# design.net
KiCad netlist of a schematic drawn in Altium Designer
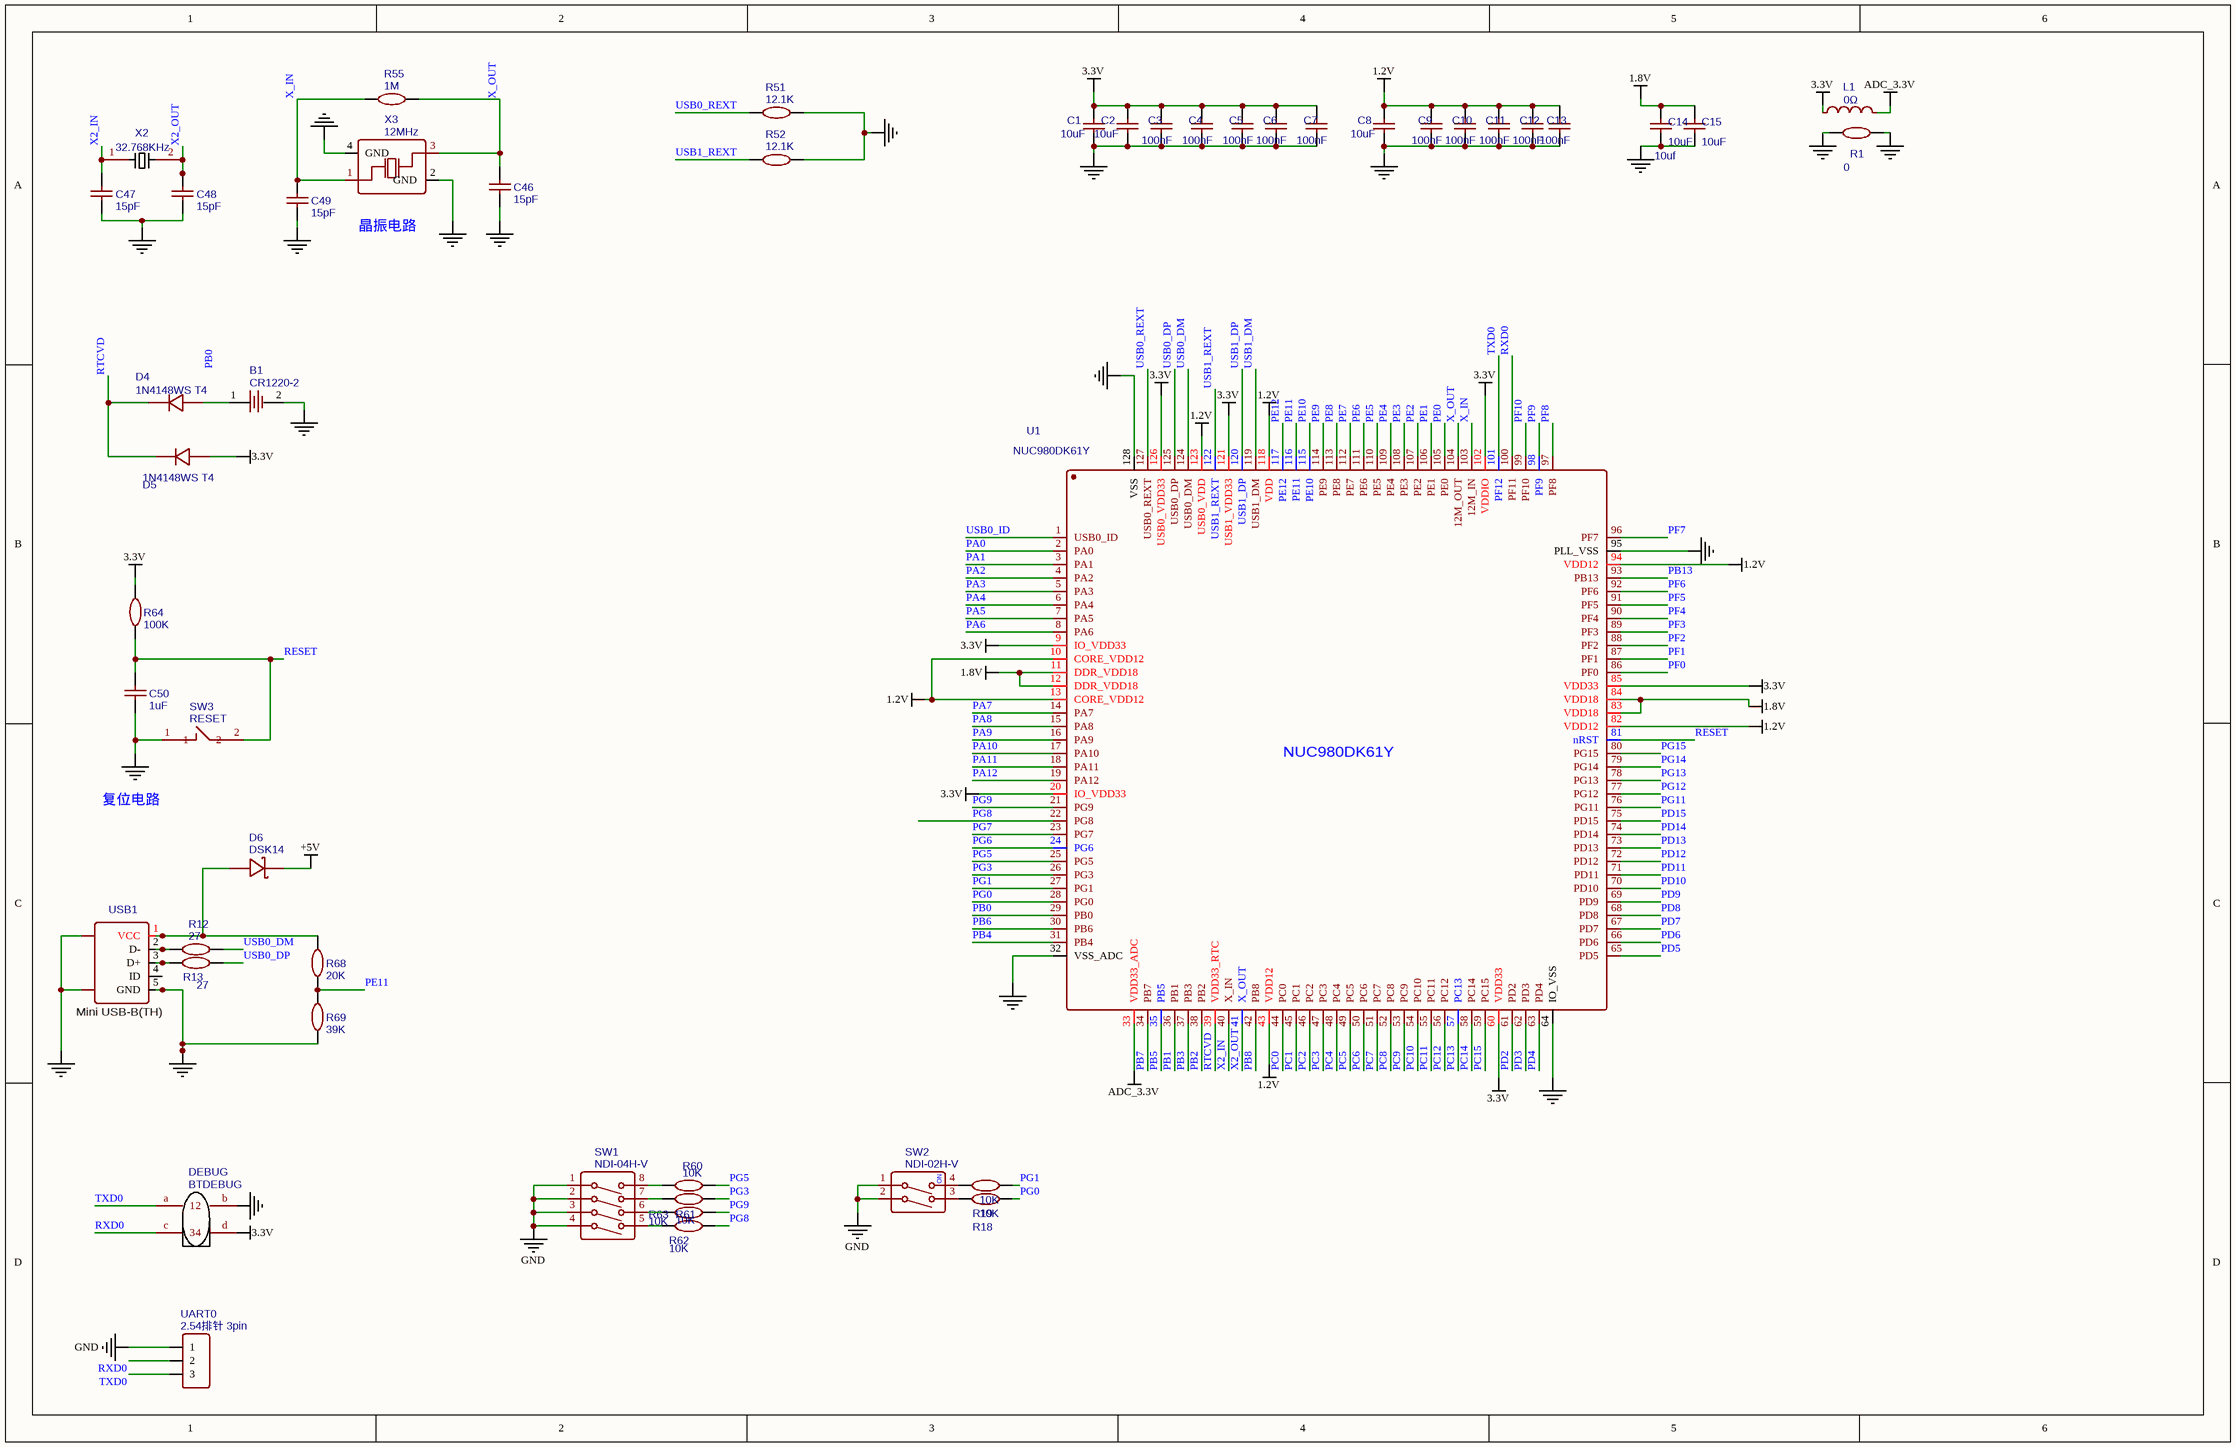
[diagram p0: 主控单元.schdoc]

(export (version "E")
  (design (tool "Eeschema 10.0.6"))
  (components
    (comp (ref "B1")
      (value "CR1220-2")
      (footprint "BATTERY-2")
      (fields (field (name "BOM_SUPPLIER PART") "C70381"))
      (libsource (lib "altium-import") (part "root_0_CR1220-2_"))
    )
    (comp (ref "C1")
      (value "10uF")
      (footprint "0805")
      (fields
        (field (name "BOM_MANUFACTURER PART") "CL21A106KAYNNNE")
        (field (name "BOM_SUPPLIER PART") "C15850")
      )
      (libsource (lib "altium-import") (part "root_1_10uF_"))
    )
    (comp (ref "C2")
      (value "10uF")
      (footprint "0805")
      (fields
        (field (name "BOM_MANUFACTURER PART") "CL21A106KAYNNNE")
        (field (name "BOM_SUPPLIER PART") "C15850")
      )
      (libsource (lib "altium-import") (part "root_1_10uF_"))
    )
    (comp (ref "C3")
      (value "100nF")
      (footprint "0402")
      (fields
        (field (name "BOM_MANUFACTURER PART") "CL05B104KO5NNNC")
        (field (name "BOM_SUPPLIER PART") "C1525")
      )
      (libsource (lib "altium-import") (part "root_1_100nF_"))
    )
    (comp (ref "C4")
      (value "100nF")
      (footprint "0402")
      (fields
        (field (name "BOM_MANUFACTURER PART") "CL05B104KO5NNNC")
        (field (name "BOM_SUPPLIER PART") "C1525")
      )
      (libsource (lib "altium-import") (part "root_1_100nF_"))
    )
    (comp (ref "C5")
      (value "100nF")
      (footprint "0402")
      (fields
        (field (name "BOM_MANUFACTURER PART") "CL05B104KO5NNNC")
        (field (name "BOM_SUPPLIER PART") "C1525")
      )
      (libsource (lib "altium-import") (part "root_1_100nF_"))
    )
    (comp (ref "C6")
      (value "100nF")
      (footprint "0402")
      (fields
        (field (name "BOM_MANUFACTURER PART") "CL05B104KO5NNNC")
        (field (name "BOM_SUPPLIER PART") "C1525")
      )
      (libsource (lib "altium-import") (part "root_1_100nF_"))
    )
    (comp (ref "C7")
      (value "100nF")
      (footprint "0402")
      (fields
        (field (name "BOM_MANUFACTURER PART") "CL05B104KO5NNNC")
        (field (name "BOM_SUPPLIER PART") "C1525")
      )
      (libsource (lib "altium-import") (part "root_1_100nF_"))
    )
    (comp (ref "C8")
      (value "10uF")
      (footprint "0805")
      (fields
        (field (name "BOM_MANUFACTURER PART") "CL21A106KAYNNNE")
        (field (name "BOM_SUPPLIER PART") "C15850")
      )
      (libsource (lib "altium-import") (part "root_1_10uF_"))
    )
    (comp (ref "C9")
      (value "100nF")
      (footprint "0402")
      (fields
        (field (name "BOM_MANUFACTURER PART") "CL05B104KO5NNNC")
        (field (name "BOM_SUPPLIER PART") "C1525")
      )
      (libsource (lib "altium-import") (part "root_1_100nF_"))
    )
    (comp (ref "C10")
      (value "100nF")
      (footprint "0402")
      (fields
        (field (name "BOM_MANUFACTURER PART") "CL05B104KO5NNNC")
        (field (name "BOM_SUPPLIER PART") "C1525")
      )
      (libsource (lib "altium-import") (part "root_1_100nF_"))
    )
    (comp (ref "C11")
      (value "100nF")
      (footprint "0402")
      (fields
        (field (name "BOM_MANUFACTURER PART") "CL05B104KO5NNNC")
        (field (name "BOM_SUPPLIER PART") "C1525")
      )
      (libsource (lib "altium-import") (part "root_1_100nF_"))
    )
    (comp (ref "C12")
      (value "100nF")
      (footprint "0402")
      (fields
        (field (name "BOM_MANUFACTURER PART") "CL05B104KO5NNNC")
        (field (name "BOM_SUPPLIER PART") "C1525")
      )
      (libsource (lib "altium-import") (part "root_1_100nF_"))
    )
    (comp (ref "C13")
      (value "100nF")
      (footprint "0402")
      (fields
        (field (name "BOM_MANUFACTURER PART") "CL05B104KO5NNNC")
        (field (name "BOM_SUPPLIER PART") "C1525")
      )
      (libsource (lib "altium-import") (part "root_1_100nF_"))
    )
    (comp (ref "C14")
      (value "10uF")
      (footprint "0805")
      (fields
        (field (name "BOM_MANUFACTURER PART") "CL21A106KAYNNNE")
        (field (name "BOM_SUPPLIER PART") "C15850")
      )
      (libsource (lib "altium-import") (part "root_1_10uF_"))
    )
    (comp (ref "C15")
      (value "10uF")
      (footprint "0805")
      (fields
        (field (name "BOM_MANUFACTURER PART") "CL21A106KAYNNNE")
        (field (name "BOM_SUPPLIER PART") "C15850")
      )
      (libsource (lib "altium-import") (part "root_1_10uF_"))
    )
    (comp (ref "C46")
      (value "15pF")
      (footprint "0402")
      (fields
        (field (name "BOM_MANUFACTURER PART") "0402CG150J500NT")
        (field (name "BOM_SUPPLIER PART") "C1548")
      )
      (libsource (lib "altium-import") (part "root_1_15pF_"))
    )
    (comp (ref "C47")
      (value "15pF")
      (footprint "0402")
      (fields
        (field (name "BOM_MANUFACTURER PART") "0402CG150J500NT")
        (field (name "BOM_SUPPLIER PART") "C1548")
      )
      (libsource (lib "altium-import") (part "root_1_15pF_"))
    )
    (comp (ref "C48")
      (value "15pF")
      (footprint "0402")
      (fields
        (field (name "BOM_MANUFACTURER PART") "0402CG150J500NT")
        (field (name "BOM_SUPPLIER PART") "C1548")
      )
      (libsource (lib "altium-import") (part "root_1_15pF_"))
    )
    (comp (ref "C49")
      (value "15pF")
      (footprint "0402")
      (fields
        (field (name "BOM_MANUFACTURER PART") "0402CG150J500NT")
        (field (name "BOM_SUPPLIER PART") "C1548")
      )
      (libsource (lib "altium-import") (part "root_1_15pF_"))
    )
    (comp (ref "C50")
      (value "1uF")
      (footprint "0603")
      (fields
        (field (name "BOM_MANUFACTURER PART") "CL10A105KB8NNNC")
        (field (name "BOM_SUPPLIER PART") "C15849")
      )
      (libsource (lib "altium-import") (part "root_1_1uF_"))
    )
    (comp (ref "D4")
      (value "1N4148WS T4")
      (footprint "SOD-323")
      (fields (field (name "BOM_SUPPLIER PART") "C2128"))
      (libsource (lib "altium-import") (part "root_2_1N4148WS T4_"))
    )
    (comp (ref "D5")
      (value "1N4148WS T4")
      (footprint "SOD-323")
      (fields (field (name "BOM_SUPPLIER PART") "C2128"))
      (libsource (lib "altium-import") (part "root_2_1N4148WS T4_"))
    )
    (comp (ref "D6")
      (value "DSK14")
      (footprint "SOD-123")
      (fields (field (name "BOM_SUPPLIER PART") "C37049"))
      (libsource (lib "altium-import") (part "root_0_DSK14_"))
    )
    (comp (ref "DEBUG")
      (value "BTDEBUG")
      (footprint "4PINO")
      (fields (field (name "BOM_MANUFACTURER PART") "?") (field (name "CONTRIBUTOR") "wode320"))
      (libsource (lib "altium-import") (part "root_0_BTDEBUG_"))
    )
    (comp (ref "L1")
      (value "0Ω")
      (footprint "0603")
      (fields
        (field (name "BOM_MANUFACTURER PART") "CBG160808U000T")
        (field (name "BOM_SUPPLIER PART") "C43163")
      )
      (libsource (lib "altium-import") (part "root_0_0Ω_"))
    )
    (comp (ref "R1")
      (value "0")
      (footprint "0603")
      (fields
        (field (name "BOM_MANUFACTURER PART") "0603WAF0000T5E")
        (field (name "BOM_SUPPLIER PART") "C21189")
      )
      (libsource (lib "altium-import") (part "root_0_0_"))
    )
    (comp (ref "R12")
      (value "27")
      (footprint "0603")
      (fields
        (field (name "BOM_MANUFACTURER PART") "0603WAF270JT5E")
        (field (name "BOM_SUPPLIER PART") "C25190")
      )
      (libsource (lib "altium-import") (part "root_0_27_"))
    )
    (comp (ref "R13")
      (value "27")
      (footprint "0603")
      (fields
        (field (name "BOM_MANUFACTURER PART") "0603WAF270JT5E")
        (field (name "BOM_SUPPLIER PART") "C25190")
      )
      (libsource (lib "altium-import") (part "root_0_27_"))
    )
    (comp (ref "R18")
      (value "10K")
      (footprint "0603")
      (fields
        (field (name "BOM_MANUFACTURER PART") "0603WAF1002T5E")
        (field (name "BOM_SUPPLIER PART") "C25804")
      )
      (libsource (lib "altium-import") (part "root_2_10K_"))
    )
    (comp (ref "R19")
      (value "10K")
      (footprint "0603")
      (fields
        (field (name "BOM_MANUFACTURER PART") "0603WAF1002T5E")
        (field (name "BOM_SUPPLIER PART") "C25804")
      )
      (libsource (lib "altium-import") (part "root_2_10K_"))
    )
    (comp (ref "R51")
      (value "12.1K")
      (footprint "0603")
      (fields
        (field (name "BOM_MANUFACTURER PART") "0603WAF1212T5E")
        (field (name "BOM_SUPPLIER PART") "C22864")
      )
      (libsource (lib "altium-import") (part "root_2_12.1K_"))
    )
    (comp (ref "R52")
      (value "12.1K")
      (footprint "0603")
      (fields
        (field (name "BOM_MANUFACTURER PART") "0603WAF1212T5E")
        (field (name "BOM_SUPPLIER PART") "C22864")
      )
      (libsource (lib "altium-import") (part "root_2_12.1K_"))
    )
    (comp (ref "R55")
      (value "1M")
      (footprint "0402")
      (fields
        (field (name "BOM_MANUFACTURER PART") "0402WGF1004TCE")
        (field (name "BOM_SUPPLIER PART") "C26083")
      )
      (libsource (lib "altium-import") (part "root_0_1M_"))
    )
    (comp (ref "R60")
      (value "10K")
      (footprint "0603")
      (fields
        (field (name "BOM_MANUFACTURER PART") "0603WAF1002T5E")
        (field (name "BOM_SUPPLIER PART") "C25804")
      )
      (libsource (lib "altium-import") (part "root_2_10K_"))
    )
    (comp (ref "R61")
      (value "10K")
      (footprint "0603")
      (fields
        (field (name "BOM_MANUFACTURER PART") "0603WAF1002T5E")
        (field (name "BOM_SUPPLIER PART") "C25804")
      )
      (libsource (lib "altium-import") (part "root_2_10K_"))
    )
    (comp (ref "R62")
      (value "10K")
      (footprint "0603")
      (fields
        (field (name "BOM_MANUFACTURER PART") "0603WAF1002T5E")
        (field (name "BOM_SUPPLIER PART") "C25804")
      )
      (libsource (lib "altium-import") (part "root_2_10K_"))
    )
    (comp (ref "R63")
      (value "10K")
      (footprint "0603")
      (fields
        (field (name "BOM_MANUFACTURER PART") "0603WAF1002T5E")
        (field (name "BOM_SUPPLIER PART") "C25804")
      )
      (libsource (lib "altium-import") (part "root_2_10K_"))
    )
    (comp (ref "R64")
      (value "100K")
      (footprint "0603")
      (fields
        (field (name "BOM_MANUFACTURER PART") "0603WAF1003T5E")
        (field (name "BOM_SUPPLIER PART") "C25803")
      )
      (libsource (lib "altium-import") (part "root_1_100K_"))
    )
    (comp (ref "R68")
      (value "20K")
      (footprint "0402")
      (fields
        (field (name "BOM_MANUFACTURER PART") "0402WGF2002TCE")
        (field (name "BOM_SUPPLIER PART") "C25765")
      )
      (libsource (lib "altium-import") (part "root_1_20K_"))
    )
    (comp (ref "R69")
      (value "39K")
      (footprint "0402")
      (fields
        (field (name "BOM_MANUFACTURER PART") "0402WGF3902TCE")
        (field (name "BOM_SUPPLIER PART") "C25783")
      )
      (libsource (lib "altium-import") (part "root_1_39K_"))
    )
    (comp (ref "SW1")
      (value "NDI-04H-V")
      (footprint "NDI-04H-V")
      (fields (field (name "BOM_SUPPLIER PART") "C225000") (field (name "CONTRIBUTOR") "LCSC"))
      (libsource (lib "altium-import") (part "root_3_NDI-04H-V_"))
    )
    (comp (ref "SW2")
      (value "NDI-02H-V")
      (footprint "NDI-02H-V")
      (fields (field (name "BOM_SUPPLIER PART") "C224999") (field (name "CONTRIBUTOR") "LCSC"))
      (libsource (lib "altium-import") (part "root_3_NDI-02H-V_"))
    )
    (comp (ref "SW3")
      (value "RESET")
      (footprint "KEY-TOUCH-SMD-6.0*3.5*H-(A)")
      (fields
        (field (name "BOM_SUPPLIER PART") "C318823")
        (field (name "BOM_MANUFACTURER PART") "1TS002B-1900-4300")
        (field (name "CONTRIBUTOR") "LCSC")
      )
      (libsource (lib "altium-import") (part "root_0_RESET_"))
    )
    (comp (ref "U1")
      (value "NUC980DK61Y")
      (footprint "LQFP-128_14X14X04P")
      (fields (field (name "BOM_MANUFACTURER PART") "?") (field (name "CONTRIBUTOR") "13603072355"))
      (libsource (lib "altium-import") (part "root_0_NUC980DK61Y_"))
    )
    (comp (ref "UART0")
      (value "2.54排针 3pin")
      (footprint "HDR-3X1/2.54")
      (fields
        (field (name "BOM_MANUFACTURER PART") "Header2.54mm 1*3P")
        (field (name "BOM_SUPPLIER PART") "C49257")
        (field (name "CONTRIBUTOR") "yds432427")
      )
      (libsource (lib "altium-import") (part "root_0_2.54排针 3pin_"))
    )
    (comp (ref "USB1")
      (value "Mini USB-B 5P-Female-TH_C46398")
      (footprint "USB-MINI-2")
      (fields
        (field (name "BOM_MANUFACTURER PART") "MINI 5PFemale90Degree plate four feet copper shell LCPVinyl")
        (field (name "BOM_SUPPLIER PART") "C46398")
      )
      (libsource (lib "altium-import") (part "root_0_Mini USB-B 5P-Female-TH_C46398_"))
    )
    (comp (ref "X2")
      (value "32.768KHz")
      (footprint "SMD-3215_2P")
      (fields
        (field (name "BOM_MANUFACTURER PART") "Q13FC1350000400")
        (field (name "BOM_SUPPLIER PART") "C32346")
      )
      (libsource (lib "altium-import") (part "root_0_32.768KHz_"))
    )
    (comp (ref "X3")
      (value "12MHz")
      (footprint "OSC-YSX-3225_4P")
      (fields
        (field (name "BOM_MANUFACTURER PART") "X322512MSB4SI")
        (field (name "BOM_SUPPLIER PART") "C9002")
      )
      (libsource (lib "altium-import") (part "root_0_12MHz_"))
    )
  )
  (nets
    (net (code "1") (name "+5V") (class "Default")
      (node (ref "D6") (pin "2") (pinfunction "K_2") (pintype "passive"))
    )
    (net (code "2") (name "/PA0") (class "Default")
      (node (ref "U1") (pin "2") (pinfunction "PA0_2") (pintype "passive"))
    )
    (net (code "3") (name "/PA1") (class "Default")
      (node (ref "U1") (pin "3") (pinfunction "PA1_3") (pintype "passive"))
    )
    (net (code "4") (name "/PA2") (class "Default")
      (node (ref "U1") (pin "4") (pinfunction "PA2_4") (pintype "passive"))
    )
    (net (code "5") (name "/PA3") (class "Default")
      (node (ref "U1") (pin "5") (pinfunction "PA3_5") (pintype "passive"))
    )
    (net (code "6") (name "/PA4") (class "Default")
      (node (ref "U1") (pin "6") (pinfunction "PA4_6") (pintype "passive"))
    )
    (net (code "7") (name "/PA5") (class "Default")
      (node (ref "U1") (pin "7") (pinfunction "PA5_7") (pintype "passive"))
    )
    (net (code "8") (name "/PA6") (class "Default")
      (node (ref "U1") (pin "8") (pinfunction "PA6_8") (pintype "passive"))
    )
    (net (code "9") (name "/PA7") (class "Default")
      (node (ref "U1") (pin "14") (pinfunction "PA7_14") (pintype "passive"))
    )
    (net (code "10") (name "/PA8") (class "Default")
      (node (ref "U1") (pin "15") (pinfunction "PA8_15") (pintype "passive"))
    )
    (net (code "11") (name "/PA9") (class "Default")
      (node (ref "U1") (pin "16") (pinfunction "PA9_16") (pintype "passive"))
    )
    (net (code "12") (name "/PA10") (class "Default")
      (node (ref "U1") (pin "17") (pinfunction "PA10_17") (pintype "passive"))
    )
    (net (code "13") (name "/PA11") (class "Default")
      (node (ref "U1") (pin "18") (pinfunction "PA11_18") (pintype "passive"))
    )
    (net (code "14") (name "/PA12") (class "Default")
      (node (ref "U1") (pin "19") (pinfunction "PA12_19") (pintype "passive"))
    )
    (net (code "15") (name "/PB0") (class "Default")
      (node (ref "U1") (pin "29") (pinfunction "PB0_29") (pintype "passive"))
    )
    (net (code "16") (name "/PB1") (class "Default")
      (node (ref "U1") (pin "36") (pinfunction "PB1_36") (pintype "passive"))
    )
    (net (code "17") (name "/PB2") (class "Default")
      (node (ref "U1") (pin "38") (pinfunction "PB2_38") (pintype "passive"))
    )
    (net (code "18") (name "/PB3") (class "Default")
      (node (ref "U1") (pin "37") (pinfunction "PB3_37") (pintype "passive"))
    )
    (net (code "19") (name "/PB4") (class "Default")
      (node (ref "U1") (pin "31") (pinfunction "PB4_31") (pintype "passive"))
    )
    (net (code "20") (name "/PB5") (class "Default")
      (node (ref "U1") (pin "35") (pinfunction "PB5_35") (pintype "passive"))
    )
    (net (code "21") (name "/PB6") (class "Default")
      (node (ref "U1") (pin "30") (pinfunction "PB6_30") (pintype "passive"))
    )
    (net (code "22") (name "/PB7") (class "Default")
      (node (ref "U1") (pin "34") (pinfunction "PB7_34") (pintype "passive"))
    )
    (net (code "23") (name "/PB8") (class "Default")
      (node (ref "U1") (pin "42") (pinfunction "PB8_42") (pintype "passive"))
    )
    (net (code "24") (name "/PB13") (class "Default")
      (node (ref "U1") (pin "93") (pinfunction "PB13_93") (pintype "passive"))
    )
    (net (code "25") (name "/PC0") (class "Default")
      (node (ref "U1") (pin "44") (pinfunction "PC0_44") (pintype "passive"))
    )
    (net (code "26") (name "/PC1") (class "Default")
      (node (ref "U1") (pin "45") (pinfunction "PC1_45") (pintype "passive"))
    )
    (net (code "27") (name "/PC2") (class "Default")
      (node (ref "U1") (pin "46") (pinfunction "PC2_46") (pintype "passive"))
    )
    (net (code "28") (name "/PC3") (class "Default")
      (node (ref "U1") (pin "47") (pinfunction "PC3_47") (pintype "passive"))
    )
    (net (code "29") (name "/PC4") (class "Default")
      (node (ref "U1") (pin "48") (pinfunction "PC4_48") (pintype "passive"))
    )
    (net (code "30") (name "/PC5") (class "Default")
      (node (ref "U1") (pin "49") (pinfunction "PC5_49") (pintype "passive"))
    )
    (net (code "31") (name "/PC6") (class "Default")
      (node (ref "U1") (pin "50") (pinfunction "PC6_50") (pintype "passive"))
    )
    (net (code "32") (name "/PC7") (class "Default")
      (node (ref "U1") (pin "51") (pinfunction "PC7_51") (pintype "passive"))
    )
    (net (code "33") (name "/PC8") (class "Default")
      (node (ref "U1") (pin "52") (pinfunction "PC8_52") (pintype "passive"))
    )
    (net (code "34") (name "/PC9") (class "Default")
      (node (ref "U1") (pin "53") (pinfunction "PC9_53") (pintype "passive"))
    )
    (net (code "35") (name "/PC10") (class "Default")
      (node (ref "U1") (pin "54") (pinfunction "PC10_54") (pintype "passive"))
    )
    (net (code "36") (name "/PC11") (class "Default")
      (node (ref "U1") (pin "55") (pinfunction "PC11_55") (pintype "passive"))
    )
    (net (code "37") (name "/PC12") (class "Default")
      (node (ref "U1") (pin "56") (pinfunction "PC12_56") (pintype "passive"))
    )
    (net (code "38") (name "/PC13") (class "Default")
      (node (ref "U1") (pin "57") (pinfunction "PC13_57") (pintype "passive"))
    )
    (net (code "39") (name "/PC14") (class "Default")
      (node (ref "U1") (pin "58") (pinfunction "PC14_58") (pintype "passive"))
    )
    (net (code "40") (name "/PC15") (class "Default")
      (node (ref "U1") (pin "59") (pinfunction "PC15_59") (pintype "passive"))
    )
    (net (code "41") (name "/PD2") (class "Default")
      (node (ref "U1") (pin "61") (pinfunction "PD2_61") (pintype "passive"))
    )
    (net (code "42") (name "/PD3") (class "Default")
      (node (ref "U1") (pin "62") (pinfunction "PD3_62") (pintype "passive"))
    )
    (net (code "43") (name "/PD4") (class "Default")
      (node (ref "U1") (pin "63") (pinfunction "PD4_63") (pintype "passive"))
    )
    (net (code "44") (name "/PD5") (class "Default")
      (node (ref "U1") (pin "65") (pinfunction "PD5_65") (pintype "passive"))
    )
    (net (code "45") (name "/PD6") (class "Default")
      (node (ref "U1") (pin "66") (pinfunction "PD6_66") (pintype "passive"))
    )
    (net (code "46") (name "/PD7") (class "Default")
      (node (ref "U1") (pin "67") (pinfunction "PD7_67") (pintype "passive"))
    )
    (net (code "47") (name "/PD8") (class "Default")
      (node (ref "U1") (pin "68") (pinfunction "PD8_68") (pintype "passive"))
    )
    (net (code "48") (name "/PD9") (class "Default")
      (node (ref "U1") (pin "69") (pinfunction "PD9_69") (pintype "passive"))
    )
    (net (code "49") (name "/PD10") (class "Default")
      (node (ref "U1") (pin "70") (pinfunction "PD10_70") (pintype "passive"))
    )
    (net (code "50") (name "/PD11") (class "Default")
      (node (ref "U1") (pin "71") (pinfunction "PD11_71") (pintype "passive"))
    )
    (net (code "51") (name "/PD12") (class "Default")
      (node (ref "U1") (pin "72") (pinfunction "PD12_72") (pintype "passive"))
    )
    (net (code "52") (name "/PD13") (class "Default")
      (node (ref "U1") (pin "73") (pinfunction "PD13_73") (pintype "passive"))
    )
    (net (code "53") (name "/PD14") (class "Default")
      (node (ref "U1") (pin "74") (pinfunction "PD14_74") (pintype "passive"))
    )
    (net (code "54") (name "/PD15") (class "Default")
      (node (ref "U1") (pin "75") (pinfunction "PD15_75") (pintype "passive"))
    )
    (net (code "55") (name "/PE0") (class "Default")
      (node (ref "U1") (pin "105") (pinfunction "PE0_105") (pintype "passive"))
    )
    (net (code "56") (name "/PE1") (class "Default")
      (node (ref "U1") (pin "106") (pinfunction "PE1_106") (pintype "passive"))
    )
    (net (code "57") (name "/PE2") (class "Default")
      (node (ref "U1") (pin "107") (pinfunction "PE2_107") (pintype "passive"))
    )
    (net (code "58") (name "/PE3") (class "Default")
      (node (ref "U1") (pin "108") (pinfunction "PE3_108") (pintype "passive"))
    )
    (net (code "59") (name "/PE4") (class "Default")
      (node (ref "U1") (pin "109") (pinfunction "PE4_109") (pintype "passive"))
    )
    (net (code "60") (name "/PE5") (class "Default")
      (node (ref "U1") (pin "110") (pinfunction "PE5_110") (pintype "passive"))
    )
    (net (code "61") (name "/PE6") (class "Default")
      (node (ref "U1") (pin "111") (pinfunction "PE6_111") (pintype "passive"))
    )
    (net (code "62") (name "/PE7") (class "Default")
      (node (ref "U1") (pin "112") (pinfunction "PE7_112") (pintype "passive"))
    )
    (net (code "63") (name "/PE8") (class "Default")
      (node (ref "U1") (pin "113") (pinfunction "PE8_113") (pintype "passive"))
    )
    (net (code "64") (name "/PE9") (class "Default")
      (node (ref "U1") (pin "114") (pinfunction "PE9_114") (pintype "passive"))
    )
    (net (code "65") (name "/PE10") (class "Default")
      (node (ref "U1") (pin "115") (pinfunction "PE10_115") (pintype "passive"))
    )
    (net (code "66") (name "/PE11") (class "Default")
      (node (ref "R68") (pin "1") (pinfunction "1_1") (pintype "passive"))
      (node (ref "R69") (pin "2") (pinfunction "2_2") (pintype "passive"))
      (node (ref "U1") (pin "116") (pinfunction "PE11_116") (pintype "passive"))
    )
    (net (code "67") (name "/PE12") (class "Default")
      (node (ref "U1") (pin "117") (pinfunction "PE12_117") (pintype "passive"))
    )
    (net (code "68") (name "/PF0") (class "Default")
      (node (ref "U1") (pin "86") (pinfunction "PF0_86") (pintype "passive"))
    )
    (net (code "69") (name "/PF1") (class "Default")
      (node (ref "U1") (pin "87") (pinfunction "PF1_87") (pintype "passive"))
    )
    (net (code "70") (name "/PF2") (class "Default")
      (node (ref "U1") (pin "88") (pinfunction "PF2_88") (pintype "passive"))
    )
    (net (code "71") (name "/PF3") (class "Default")
      (node (ref "U1") (pin "89") (pinfunction "PF3_89") (pintype "passive"))
    )
    (net (code "72") (name "/PF4") (class "Default")
      (node (ref "U1") (pin "90") (pinfunction "PF4_90") (pintype "passive"))
    )
    (net (code "73") (name "/PF5") (class "Default")
      (node (ref "U1") (pin "91") (pinfunction "PF5_91") (pintype "passive"))
    )
    (net (code "74") (name "/PF6") (class "Default")
      (node (ref "U1") (pin "92") (pinfunction "PF6_92") (pintype "passive"))
    )
    (net (code "75") (name "/PF7") (class "Default")
      (node (ref "U1") (pin "96") (pinfunction "PF7_96") (pintype "passive"))
    )
    (net (code "76") (name "/PF8") (class "Default")
      (node (ref "U1") (pin "97") (pinfunction "PF8_97") (pintype "passive"))
    )
    (net (code "77") (name "/PF9") (class "Default")
      (node (ref "U1") (pin "98") (pinfunction "PF9_98") (pintype "passive"))
    )
    (net (code "78") (name "/PF10") (class "Default")
      (node (ref "U1") (pin "99") (pinfunction "PF10_99") (pintype "passive"))
    )
    (net (code "79") (name "/PG0") (class "Default")
      (node (ref "R18") (pin "1") (pinfunction "1_1") (pintype "passive"))
      (node (ref "U1") (pin "28") (pinfunction "PG0_28") (pintype "passive"))
    )
    (net (code "80") (name "/PG1") (class "Default")
      (node (ref "R19") (pin "1") (pinfunction "1_1") (pintype "passive"))
      (node (ref "U1") (pin "27") (pinfunction "PG1_27") (pintype "passive"))
    )
    (net (code "81") (name "/PG3") (class "Default")
      (node (ref "R61") (pin "1") (pinfunction "1_1") (pintype "passive"))
      (node (ref "U1") (pin "26") (pinfunction "PG3_26") (pintype "passive"))
    )
    (net (code "82") (name "/PG5") (class "Default")
      (node (ref "R60") (pin "1") (pinfunction "1_1") (pintype "passive"))
      (node (ref "U1") (pin "25") (pinfunction "PG5_25") (pintype "passive"))
    )
    (net (code "83") (name "/PG6") (class "Default")
      (node (ref "U1") (pin "24") (pinfunction "PG6_24") (pintype "passive"))
    )
    (net (code "84") (name "/PG7") (class "Default")
      (node (ref "U1") (pin "23") (pinfunction "PG7_23") (pintype "passive"))
    )
    (net (code "85") (name "/PG8") (class "Default")
      (node (ref "R62") (pin "1") (pinfunction "1_1") (pintype "passive"))
      (node (ref "U1") (pin "22") (pinfunction "PG8_22") (pintype "passive"))
    )
    (net (code "86") (name "/PG9") (class "Default")
      (node (ref "R63") (pin "1") (pinfunction "1_1") (pintype "passive"))
      (node (ref "U1") (pin "21") (pinfunction "PG9_21") (pintype "passive"))
    )
    (net (code "87") (name "/PG11") (class "Default")
      (node (ref "U1") (pin "76") (pinfunction "PG11_76") (pintype "passive"))
    )
    (net (code "88") (name "/PG12") (class "Default")
      (node (ref "U1") (pin "77") (pinfunction "PG12_77") (pintype "passive"))
    )
    (net (code "89") (name "/PG13") (class "Default")
      (node (ref "U1") (pin "78") (pinfunction "PG13_78") (pintype "passive"))
    )
    (net (code "90") (name "/PG14") (class "Default")
      (node (ref "U1") (pin "79") (pinfunction "PG14_79") (pintype "passive"))
    )
    (net (code "91") (name "/PG15") (class "Default")
      (node (ref "U1") (pin "80") (pinfunction "PG15_80") (pintype "passive"))
    )
    (net (code "92") (name "/RESET") (class "Default")
      (node (ref "C50") (pin "2") (pinfunction "2_2") (pintype "passive"))
      (node (ref "R64") (pin "1") (pinfunction "1_1") (pintype "passive"))
      (node (ref "SW3") (pin "2") (pinfunction "2_2") (pintype "passive"))
      (node (ref "U1") (pin "81") (pinfunction "nRST_81") (pintype "passive"))
    )
    (net (code "93") (name "/RTCVD") (class "Default")
      (node (ref "D4") (pin "2") (pinfunction "K_2") (pintype "passive"))
      (node (ref "D5") (pin "2") (pinfunction "K_2") (pintype "passive"))
      (node (ref "U1") (pin "39") (pinfunction "VDD33_RTC_39") (pintype "passive"))
    )
    (net (code "94") (name "/RXD0") (class "Default")
      (node (ref "DEBUG") (pin "c") (pinfunction "3_c") (pintype "passive"))
      (node (ref "U1") (pin "100") (pinfunction "PF11_100") (pintype "passive"))
      (node (ref "UART0") (pin "2") (pinfunction "2_2") (pintype "passive"))
    )
    (net (code "95") (name "/TXD0") (class "Default")
      (node (ref "DEBUG") (pin "a") (pinfunction "1_a") (pintype "passive"))
      (node (ref "U1") (pin "101") (pinfunction "PF12_101") (pintype "passive"))
      (node (ref "UART0") (pin "3") (pinfunction "3_3") (pintype "passive"))
    )
    (net (code "96") (name "/USB0_DM") (class "Default")
      (node (ref "R12") (pin "2") (pinfunction "2_2") (pintype "passive"))
      (node (ref "U1") (pin "124") (pinfunction "USB0_DM_124") (pintype "passive"))
    )
    (net (code "97") (name "/USB0_DP") (class "Default")
      (node (ref "R13") (pin "2") (pinfunction "2_2") (pintype "passive"))
      (node (ref "U1") (pin "125") (pinfunction "USB0_DP_125") (pintype "passive"))
    )
    (net (code "98") (name "/USB0_ID") (class "Default")
      (node (ref "U1") (pin "1") (pinfunction "USB0_ID_1") (pintype "passive"))
    )
    (net (code "99") (name "/USB0_REXT") (class "Default")
      (node (ref "R51") (pin "2") (pinfunction "2_2") (pintype "passive"))
      (node (ref "U1") (pin "127") (pinfunction "USB0_REXT_127") (pintype "passive"))
    )
    (net (code "100") (name "/USB1_DM") (class "Default")
      (node (ref "U1") (pin "119") (pinfunction "USB1_DM_119") (pintype "passive"))
    )
    (net (code "101") (name "/USB1_DP") (class "Default")
      (node (ref "U1") (pin "120") (pinfunction "USB1_DP_120") (pintype "passive"))
    )
    (net (code "102") (name "/USB1_REXT") (class "Default")
      (node (ref "R52") (pin "2") (pinfunction "2_2") (pintype "passive"))
      (node (ref "U1") (pin "122") (pinfunction "USB1_REXT_122") (pintype "passive"))
    )
    (net (code "103") (name "/X2_IN") (class "Default")
      (node (ref "C47") (pin "2") (pinfunction "2_2") (pintype "passive"))
      (node (ref "U1") (pin "40") (pinfunction "X_IN_40") (pintype "passive"))
      (node (ref "X2") (pin "1") (pinfunction "1_1") (pintype "passive"))
    )
    (net (code "104") (name "/X2_OUT") (class "Default")
      (node (ref "C48") (pin "2") (pinfunction "2_2") (pintype "passive"))
      (node (ref "U1") (pin "41") (pinfunction "X_OUT_41") (pintype "passive"))
      (node (ref "X2") (pin "2") (pinfunction "2_2") (pintype "passive"))
    )
    (net (code "105") (name "/X_IN") (class "Default")
      (node (ref "C49") (pin "2") (pinfunction "2_2") (pintype "passive"))
      (node (ref "R55") (pin "1") (pinfunction "1_1") (pintype "passive"))
      (node (ref "U1") (pin "103") (pinfunction "12M_IN_103") (pintype "passive"))
      (node (ref "X3") (pin "1") (pinfunction "OSC1_1") (pintype "passive"))
    )
    (net (code "106") (name "/X_OUT") (class "Default")
      (node (ref "C46") (pin "2") (pinfunction "2_2") (pintype "passive"))
      (node (ref "R55") (pin "2") (pinfunction "2_2") (pintype "passive"))
      (node (ref "U1") (pin "104") (pinfunction "12M_OUT_104") (pintype "passive"))
      (node (ref "X3") (pin "3") (pinfunction "OSC2_3") (pintype "passive"))
    )
    (net (code "107") (name "1.2V") (class "Default")
      (node (ref "C10") (pin "2") (pinfunction "2_2") (pintype "passive"))
      (node (ref "C11") (pin "2") (pinfunction "2_2") (pintype "passive"))
      (node (ref "C12") (pin "2") (pinfunction "2_2") (pintype "passive"))
      (node (ref "C13") (pin "2") (pinfunction "2_2") (pintype "passive"))
      (node (ref "C8") (pin "2") (pinfunction "2_2") (pintype "passive"))
      (node (ref "C9") (pin "2") (pinfunction "2_2") (pintype "passive"))
      (node (ref "U1") (pin "10") (pinfunction "CORE_VDD12_10") (pintype "passive"))
      (node (ref "U1") (pin "118") (pinfunction "VDD_118") (pintype "passive"))
      (node (ref "U1") (pin "123") (pinfunction "USB0_VDD_123") (pintype "passive"))
      (node (ref "U1") (pin "13") (pinfunction "CORE_VDD12_13") (pintype "passive"))
      (node (ref "U1") (pin "43") (pinfunction "VDD12_43") (pintype "passive"))
      (node (ref "U1") (pin "82") (pinfunction "VDD12_82") (pintype "passive"))
      (node (ref "U1") (pin "94") (pinfunction "VDD12_94") (pintype "passive"))
    )
    (net (code "108") (name "1.8V") (class "Default")
      (node (ref "C14") (pin "2") (pinfunction "2_2") (pintype "passive"))
      (node (ref "C15") (pin "2") (pinfunction "2_2") (pintype "passive"))
      (node (ref "U1") (pin "11") (pinfunction "DDR_VDD18_11") (pintype "passive"))
      (node (ref "U1") (pin "12") (pinfunction "DDR_VDD18_12") (pintype "passive"))
      (node (ref "U1") (pin "83") (pinfunction "VDD18_83") (pintype "passive"))
      (node (ref "U1") (pin "84") (pinfunction "VDD18_84") (pintype "passive"))
    )
    (net (code "109") (name "3.3V") (class "Default")
      (node (ref "C1") (pin "2") (pinfunction "2_2") (pintype "passive"))
      (node (ref "C2") (pin "2") (pinfunction "2_2") (pintype "passive"))
      (node (ref "C3") (pin "2") (pinfunction "2_2") (pintype "passive"))
      (node (ref "C4") (pin "2") (pinfunction "2_2") (pintype "passive"))
      (node (ref "C5") (pin "2") (pinfunction "2_2") (pintype "passive"))
      (node (ref "C6") (pin "2") (pinfunction "2_2") (pintype "passive"))
      (node (ref "C7") (pin "2") (pinfunction "2_2") (pintype "passive"))
      (node (ref "D5") (pin "1") (pinfunction "A_1") (pintype "passive"))
      (node (ref "DEBUG") (pin "d") (pinfunction "4_d") (pintype "passive"))
      (node (ref "L1") (pin "1") (pinfunction "1_1") (pintype "passive"))
      (node (ref "R64") (pin "2") (pinfunction "2_2") (pintype "passive"))
      (node (ref "U1") (pin "102") (pinfunction "VDDIO_102") (pintype "passive"))
      (node (ref "U1") (pin "121") (pinfunction "USB1_VDD33_121") (pintype "passive"))
      (node (ref "U1") (pin "126") (pinfunction "USB0_VDD33_126") (pintype "passive"))
      (node (ref "U1") (pin "20") (pinfunction "IO_VDD33_20") (pintype "passive"))
      (node (ref "U1") (pin "60") (pinfunction "VDD33_60") (pintype "passive"))
      (node (ref "U1") (pin "85") (pinfunction "VDD33_85") (pintype "passive"))
      (node (ref "U1") (pin "9") (pinfunction "IO_VDD33_9") (pintype "passive"))
    )
    (net (code "110") (name "ADC_3.3V") (class "Default")
      (node (ref "L1") (pin "2") (pinfunction "2_2") (pintype "passive"))
      (node (ref "U1") (pin "33") (pinfunction "VDD33_ADC_33") (pintype "passive"))
    )
    (net (code "111") (name "GND") (class "Default")
      (node (ref "B1") (pin "2") (pinfunction "2_2") (pintype "passive"))
      (node (ref "C1") (pin "1") (pinfunction "1_1") (pintype "passive"))
      (node (ref "C10") (pin "1") (pinfunction "1_1") (pintype "passive"))
      (node (ref "C11") (pin "1") (pinfunction "1_1") (pintype "passive"))
      (node (ref "C12") (pin "1") (pinfunction "1_1") (pintype "passive"))
      (node (ref "C13") (pin "1") (pinfunction "1_1") (pintype "passive"))
      (node (ref "C14") (pin "1") (pinfunction "1_1") (pintype "passive"))
      (node (ref "C15") (pin "1") (pinfunction "1_1") (pintype "passive"))
      (node (ref "C2") (pin "1") (pinfunction "1_1") (pintype "passive"))
      (node (ref "C3") (pin "1") (pinfunction "1_1") (pintype "passive"))
      (node (ref "C4") (pin "1") (pinfunction "1_1") (pintype "passive"))
      (node (ref "C46") (pin "1") (pinfunction "1_1") (pintype "passive"))
      (node (ref "C47") (pin "1") (pinfunction "1_1") (pintype "passive"))
      (node (ref "C48") (pin "1") (pinfunction "1_1") (pintype "passive"))
      (node (ref "C49") (pin "1") (pinfunction "1_1") (pintype "passive"))
      (node (ref "C5") (pin "1") (pinfunction "1_1") (pintype "passive"))
      (node (ref "C50") (pin "1") (pinfunction "1_1") (pintype "passive"))
      (node (ref "C6") (pin "1") (pinfunction "1_1") (pintype "passive"))
      (node (ref "C7") (pin "1") (pinfunction "1_1") (pintype "passive"))
      (node (ref "C8") (pin "1") (pinfunction "1_1") (pintype "passive"))
      (node (ref "C9") (pin "1") (pinfunction "1_1") (pintype "passive"))
      (node (ref "DEBUG") (pin "b") (pinfunction "2_b") (pintype "passive"))
      (node (ref "R1") (pin "1") (pinfunction "1_1") (pintype "passive"))
      (node (ref "R51") (pin "1") (pinfunction "1_1") (pintype "passive"))
      (node (ref "R52") (pin "1") (pinfunction "1_1") (pintype "passive"))
      (node (ref "R69") (pin "1") (pinfunction "1_1") (pintype "passive"))
      (node (ref "SW1") (pin "1") (pinfunction "1_1") (pintype "passive"))
      (node (ref "SW1") (pin "2") (pinfunction "2_2") (pintype "passive"))
      (node (ref "SW1") (pin "3") (pinfunction "3_3") (pintype "passive"))
      (node (ref "SW1") (pin "4") (pinfunction "4_4") (pintype "passive"))
      (node (ref "SW2") (pin "1") (pinfunction "1_1") (pintype "passive"))
      (node (ref "SW2") (pin "2") (pinfunction "2_2") (pintype "passive"))
      (node (ref "SW3") (pin "1") (pinfunction "1_1") (pintype "passive"))
      (node (ref "U1") (pin "128") (pinfunction "VSS_128") (pintype "passive"))
      (node (ref "U1") (pin "64") (pinfunction "IO_VSS_64") (pintype "passive"))
      (node (ref "U1") (pin "95") (pinfunction "PLL_VSS_95") (pintype "passive"))
      (node (ref "UART0") (pin "1") (pinfunction "1_1") (pintype "passive"))
      (node (ref "USB1") (pin "0") (pinfunction "0_0") (pintype "passive"))
      (node (ref "USB1") (pin "5") (pinfunction "GND_5") (pintype "passive"))
      (node (ref "X3") (pin "2") (pinfunction "GND_2") (pintype "passive"))
      (node (ref "X3") (pin "4") (pinfunction "GND_4") (pintype "passive"))
    )
    (net (code "112") (name "GND1") (class "Default")
      (node (ref "R1") (pin "2") (pinfunction "2_2") (pintype "passive"))
      (node (ref "U1") (pin "32") (pinfunction "VSS_ADC_32") (pintype "passive"))
    )
    (net (code "113") (name "Net-(D4-A)") (class "Default")
      (node (ref "B1") (pin "1") (pinfunction "1_1") (pintype "passive"))
      (node (ref "D4") (pin "1") (pinfunction "A_1") (pintype "passive"))
    )
    (net (code "114") (name "Net-(D6-A)") (class "Default")
      (node (ref "D6") (pin "1") (pinfunction "A_1") (pintype "passive"))
      (node (ref "R68") (pin "2") (pinfunction "2_2") (pintype "passive"))
      (node (ref "USB1") (pin "1") (pinfunction "VCC_1") (pintype "passive"))
    )
    (net (code "115") (name "Net-(R18-Pad2)") (class "Default")
      (node (ref "R18") (pin "2") (pinfunction "2_2") (pintype "passive"))
      (node (ref "SW2") (pin "3") (pinfunction "3_3") (pintype "passive"))
    )
    (net (code "116") (name "Net-(R19-Pad2)") (class "Default")
      (node (ref "R19") (pin "2") (pinfunction "2_2") (pintype "passive"))
      (node (ref "SW2") (pin "4") (pinfunction "4_4") (pintype "passive"))
    )
    (net (code "117") (name "Net-(R60-Pad2)") (class "Default")
      (node (ref "R60") (pin "2") (pinfunction "2_2") (pintype "passive"))
      (node (ref "SW1") (pin "8") (pinfunction "8_8") (pintype "passive"))
    )
    (net (code "118") (name "Net-(R61-Pad2)") (class "Default")
      (node (ref "R61") (pin "2") (pinfunction "2_2") (pintype "passive"))
      (node (ref "SW1") (pin "7") (pinfunction "7_7") (pintype "passive"))
    )
    (net (code "119") (name "Net-(R62-Pad2)") (class "Default")
      (node (ref "R62") (pin "2") (pinfunction "2_2") (pintype "passive"))
      (node (ref "SW1") (pin "5") (pinfunction "5_5") (pintype "passive"))
    )
    (net (code "120") (name "Net-(R63-Pad2)") (class "Default")
      (node (ref "R63") (pin "2") (pinfunction "2_2") (pintype "passive"))
      (node (ref "SW1") (pin "6") (pinfunction "6_6") (pintype "passive"))
    )
    (net (code "121") (name "Net-(USB1-D+)") (class "Default")
      (node (ref "R13") (pin "1") (pinfunction "1_1") (pintype "passive"))
      (node (ref "USB1") (pin "3") (pinfunction "D+_3") (pintype "passive"))
    )
    (net (code "122") (name "Net-(USB1-D-)") (class "Default")
      (node (ref "R12") (pin "1") (pinfunction "1_1") (pintype "passive"))
      (node (ref "USB1") (pin "2") (pinfunction "D-_2") (pintype "passive"))
    )
    (net (code "123") (name "unconnected-(USB1-ID-Pad4)") (class "Default")
      (node (ref "USB1") (pin "4") (pinfunction "ID_4") (pintype "passive"))
    )
  )
)
